# Zio_Qwiic_Triple_Axis_Magnetometer_MLX90.net
KiCad netlist of a schematic drawn in EAGLE
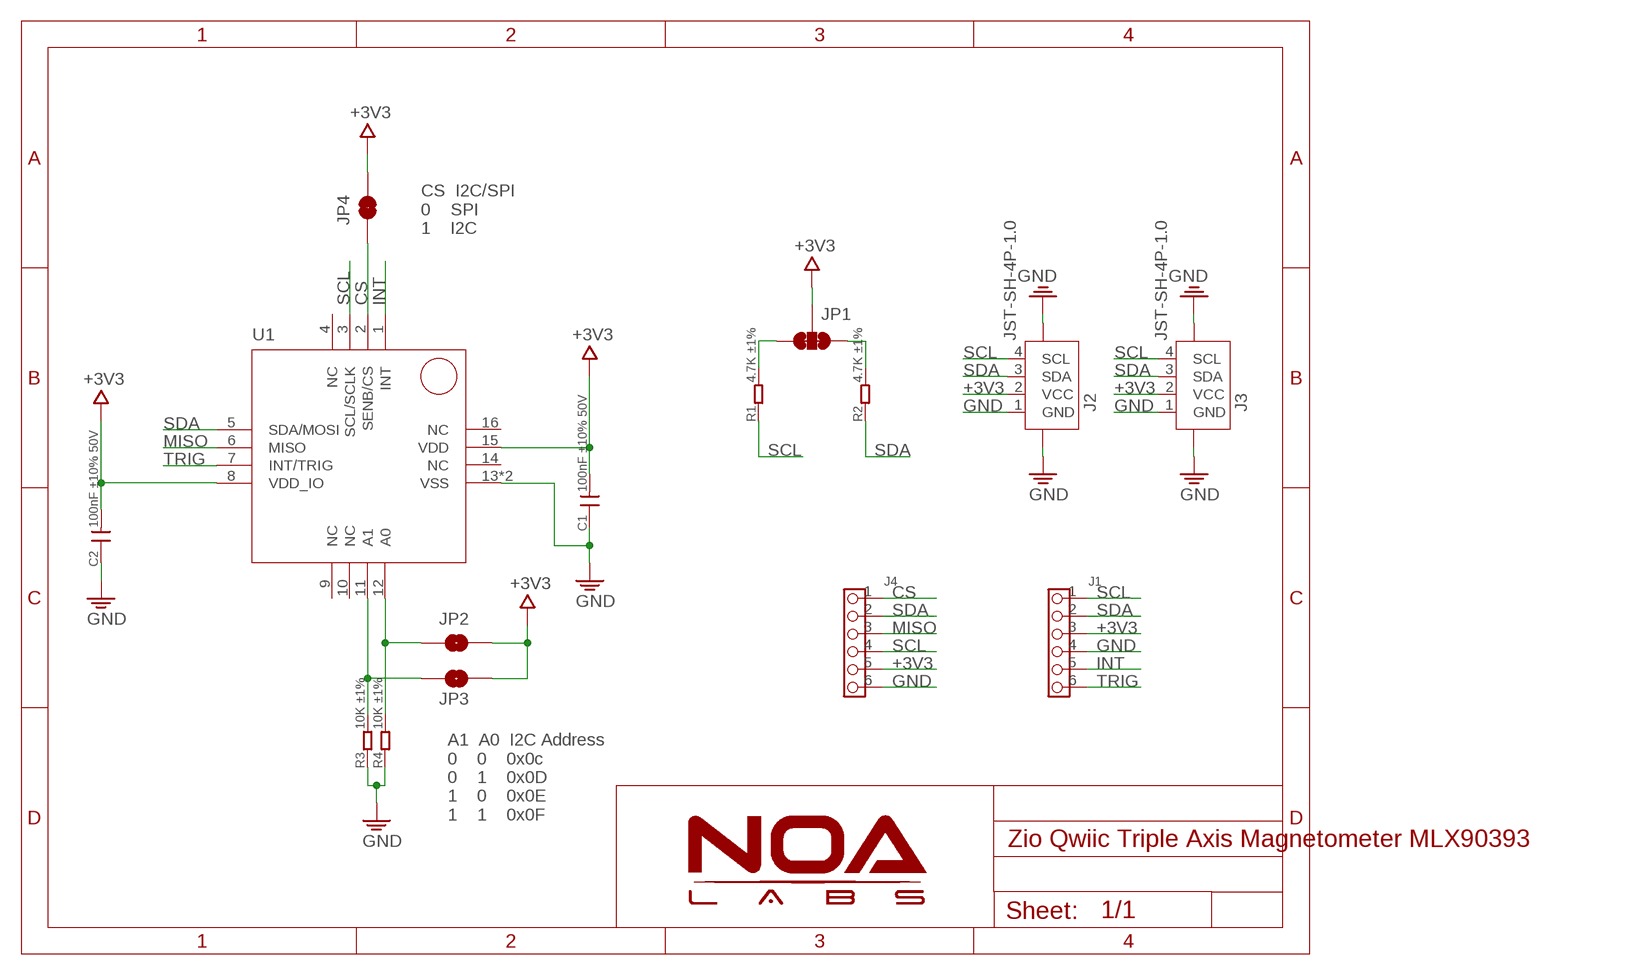
[diagram p0: schematic, sheet 1]

(export (version "E")
  (design (tool "Eeschema 10.0.6"))
  (components
    (comp (ref "C1")
      (value "100nF ±10% 50V")
      (footprint "eagle-import:C0603")
      (libsource (lib "eagle-import") (part "C-0603"))
    )
    (comp (ref "C2")
      (value "100nF ±10% 50V")
      (footprint "eagle-import:C0603")
      (libsource (lib "eagle-import") (part "C-0603"))
    )
    (comp (ref "J1")
      (value "HEADER-6P-60/35MIL")
      (footprint "eagle-import:6P-2.54-60_35MIL")
      (libsource (lib "eagle-import") (part "HEADER-6P-60/35MIL"))
    )
    (comp (ref "J2")
      (value "JST-SH-4P-1.0")
      (footprint "eagle-import:JST-SH-4P")
      (libsource (lib "eagle-import") (part "JST-SH-4P-1.0"))
    )
    (comp (ref "J3")
      (value "JST-SH-4P-1.0")
      (footprint "eagle-import:JST-SH-4P")
      (libsource (lib "eagle-import") (part "JST-SH-4P-1.0"))
    )
    (comp (ref "J4")
      (value "HEADER-6P-60/35MIL")
      (footprint "eagle-import:6P-2.54-60_35MIL")
      (libsource (lib "eagle-import") (part "HEADER-6P-60/35MIL"))
    )
    (comp (ref "JP1")
      (value "SMT-JUMPER_3_2-NC_TRACE")
      (footprint "eagle-import:SMT-JUMPER_3_2-NC_TRACE")
      (libsource (lib "eagle-import") (part "SMT-JUMPER_3_2-NC_TRACE"))
    )
    (comp (ref "JP2")
      (value "JUMPER-SMT_2_NC_PASTE_NOCREM")
      (footprint "eagle-import:SMT-JUMPER_2_NC_PASTE_SILK_NOCREM")
      (libsource (lib "eagle-import") (part "JUMPER-SMT_2_NC_PASTE_NOCREM"))
    )
    (comp (ref "JP3")
      (value "JUMPER-SMT_2_NC_PASTE_NOCREM")
      (footprint "eagle-import:SMT-JUMPER_2_NC_PASTE_SILK_NOCREM")
      (libsource (lib "eagle-import") (part "JUMPER-SMT_2_NC_PASTE_NOCREM"))
    )
    (comp (ref "JP4")
      (value "JUMPER-SMT_2_NC_TRACE")
      (footprint "eagle-import:SMT-JUMPER_2_NC_TRACE")
      (libsource (lib "eagle-import") (part "JUMPER-SMT_2_NC_TRACE"))
    )
    (comp (ref "R1")
      (value "4.7K ±1%")
      (footprint "eagle-import:R0603")
      (libsource (lib "eagle-import") (part "R-0603"))
    )
    (comp (ref "R2")
      (value "4.7K ±1%")
      (footprint "eagle-import:R0603")
      (libsource (lib "eagle-import") (part "R-0603"))
    )
    (comp (ref "R3")
      (value "10K ±1%")
      (footprint "eagle-import:R0603")
      (libsource (lib "eagle-import") (part "R-0603"))
    )
    (comp (ref "R4")
      (value "10K ±1%")
      (footprint "eagle-import:R0603")
      (libsource (lib "eagle-import") (part "R-0603"))
    )
    (comp (ref "U1")
      (value "MLX90393")
      (footprint "eagle-import:QFN16-3_3")
      (libsource (lib "eagle-import") (part "MLX90393"))
    )
  )
  (nets
    (net (code "1") (name "+3V3") (class "Default")
      (node (ref "C1") (pin "2") (pinfunction "2_2") (pintype "passive"))
      (node (ref "C2") (pin "2") (pinfunction "2_2") (pintype "passive"))
      (node (ref "J1") (pin "3") (pinfunction "3_3") (pintype "bidirectional"))
      (node (ref "J2") (pin "2") (pinfunction "VCC_2") (pintype "bidirectional"))
      (node (ref "J3") (pin "2") (pinfunction "VCC_2") (pintype "bidirectional"))
      (node (ref "J4") (pin "5") (pinfunction "5_5") (pintype "bidirectional"))
      (node (ref "JP1") (pin "2") (pinfunction "2_2") (pintype "passive"))
      (node (ref "JP2") (pin "2") (pinfunction "2_2") (pintype "passive"))
      (node (ref "JP3") (pin "2") (pinfunction "2_2") (pintype "passive"))
      (node (ref "JP4") (pin "2") (pinfunction "2_2") (pintype "passive"))
      (node (ref "U1") (pin "15") (pinfunction "VDD_15") (pintype "bidirectional"))
      (node (ref "U1") (pin "8") (pinfunction "VDD_IO_8") (pintype "bidirectional"))
    )
    (net (code "2") (name "/CS") (class "Default")
      (node (ref "J4") (pin "1") (pinfunction "1_1") (pintype "bidirectional"))
      (node (ref "JP4") (pin "1") (pinfunction "1_1") (pintype "passive"))
      (node (ref "U1") (pin "2") (pinfunction "SENB/CS_2") (pintype "bidirectional"))
    )
    (net (code "3") (name "/INT") (class "Default")
      (node (ref "J1") (pin "5") (pinfunction "5_5") (pintype "bidirectional"))
      (node (ref "U1") (pin "1") (pinfunction "INT_1") (pintype "bidirectional"))
    )
    (net (code "4") (name "/MISO") (class "Default")
      (node (ref "J4") (pin "3") (pinfunction "3_3") (pintype "bidirectional"))
      (node (ref "U1") (pin "6") (pinfunction "MISO_6") (pintype "bidirectional"))
    )
    (net (code "5") (name "/SCL") (class "Default")
      (node (ref "J1") (pin "1") (pinfunction "1_1") (pintype "bidirectional"))
      (node (ref "J2") (pin "4") (pinfunction "SCL_4") (pintype "bidirectional"))
      (node (ref "J3") (pin "4") (pinfunction "SCL_4") (pintype "bidirectional"))
      (node (ref "J4") (pin "4") (pinfunction "4_4") (pintype "bidirectional"))
      (node (ref "R1") (pin "1") (pinfunction "1_1") (pintype "passive"))
      (node (ref "U1") (pin "3") (pinfunction "SCL/SCLK_3") (pintype "bidirectional"))
    )
    (net (code "6") (name "/SDA") (class "Default")
      (node (ref "J1") (pin "2") (pinfunction "2_2") (pintype "bidirectional"))
      (node (ref "J2") (pin "3") (pinfunction "SDA_3") (pintype "bidirectional"))
      (node (ref "J3") (pin "3") (pinfunction "SDA_3") (pintype "bidirectional"))
      (node (ref "J4") (pin "2") (pinfunction "2_2") (pintype "bidirectional"))
      (node (ref "R2") (pin "1") (pinfunction "1_1") (pintype "passive"))
      (node (ref "U1") (pin "5") (pinfunction "SDA/MOSI_5") (pintype "bidirectional"))
    )
    (net (code "7") (name "/TRIG") (class "Default")
      (node (ref "J1") (pin "6") (pinfunction "6_6") (pintype "bidirectional"))
      (node (ref "U1") (pin "7") (pinfunction "INT/TRIG_7") (pintype "bidirectional"))
    )
    (net (code "8") (name "GND") (class "Default")
      (node (ref "C1") (pin "1") (pinfunction "1_1") (pintype "passive"))
      (node (ref "C2") (pin "1") (pinfunction "1_1") (pintype "passive"))
      (node (ref "J1") (pin "4") (pinfunction "4_4") (pintype "bidirectional"))
      (node (ref "J2") (pin "1") (pinfunction "GND_1") (pintype "bidirectional"))
      (node (ref "J2") (pin "NC1") (pinfunction "5_NC1") (pintype "bidirectional"))
      (node (ref "J2") (pin "NC2") (pinfunction "6_NC2") (pintype "bidirectional"))
      (node (ref "J3") (pin "1") (pinfunction "GND_1") (pintype "bidirectional"))
      (node (ref "J3") (pin "NC1") (pinfunction "5_NC1") (pintype "bidirectional"))
      (node (ref "J3") (pin "NC2") (pinfunction "6_NC2") (pintype "bidirectional"))
      (node (ref "J4") (pin "6") (pinfunction "6_6") (pintype "bidirectional"))
      (node (ref "R3") (pin "1") (pinfunction "1_1") (pintype "passive"))
      (node (ref "R4") (pin "1") (pinfunction "1_1") (pintype "passive"))
      (node (ref "U1") (pin "13") (pinfunction "VSS_13") (pintype "bidirectional"))
      (node (ref "U1") (pin "PAD") (pinfunction "VSS_PAD") (pintype "bidirectional"))
    )
    (net (code "9") (name "Net-(JP1-Pad1)") (class "Default")
      (node (ref "JP1") (pin "1") (pinfunction "1_1") (pintype "passive"))
      (node (ref "R2") (pin "2") (pinfunction "2_2") (pintype "passive"))
    )
    (net (code "10") (name "Net-(JP1-Pad3)") (class "Default")
      (node (ref "JP1") (pin "3") (pinfunction "3_3") (pintype "passive"))
      (node (ref "R1") (pin "2") (pinfunction "2_2") (pintype "passive"))
    )
    (net (code "11") (name "Net-(U1-A0)") (class "Default")
      (node (ref "JP2") (pin "1") (pinfunction "1_1") (pintype "passive"))
      (node (ref "R4") (pin "2") (pinfunction "2_2") (pintype "passive"))
      (node (ref "U1") (pin "12") (pinfunction "A0_12") (pintype "bidirectional"))
    )
    (net (code "12") (name "Net-(U1-A1)") (class "Default")
      (node (ref "JP3") (pin "1") (pinfunction "1_1") (pintype "passive"))
      (node (ref "R3") (pin "2") (pinfunction "2_2") (pintype "passive"))
      (node (ref "U1") (pin "11") (pinfunction "A1_11") (pintype "bidirectional"))
    )
    (net (code "13") (name "unconnected-(U1-NC-Pad4)") (class "Default")
      (node (ref "U1") (pin "4") (pinfunction "NC_4") (pintype "bidirectional"))
    )
    (net (code "14") (name "unconnected-(U1-NC-Pad9)") (class "Default")
      (node (ref "U1") (pin "9") (pinfunction "NC_9") (pintype "bidirectional"))
    )
    (net (code "15") (name "unconnected-(U1-NC-Pad10)") (class "Default")
      (node (ref "U1") (pin "10") (pinfunction "NC_10") (pintype "bidirectional"))
    )
    (net (code "16") (name "unconnected-(U1-NC-Pad14)") (class "Default")
      (node (ref "U1") (pin "14") (pinfunction "NC_14") (pintype "bidirectional"))
    )
    (net (code "17") (name "unconnected-(U1-NC-Pad16)") (class "Default")
      (node (ref "U1") (pin "16") (pinfunction "NC_16") (pintype "bidirectional"))
    )
  )
)
